# EEM_FMC_Carrier.net
KiCad netlist of a schematic drawn in Altium Designer
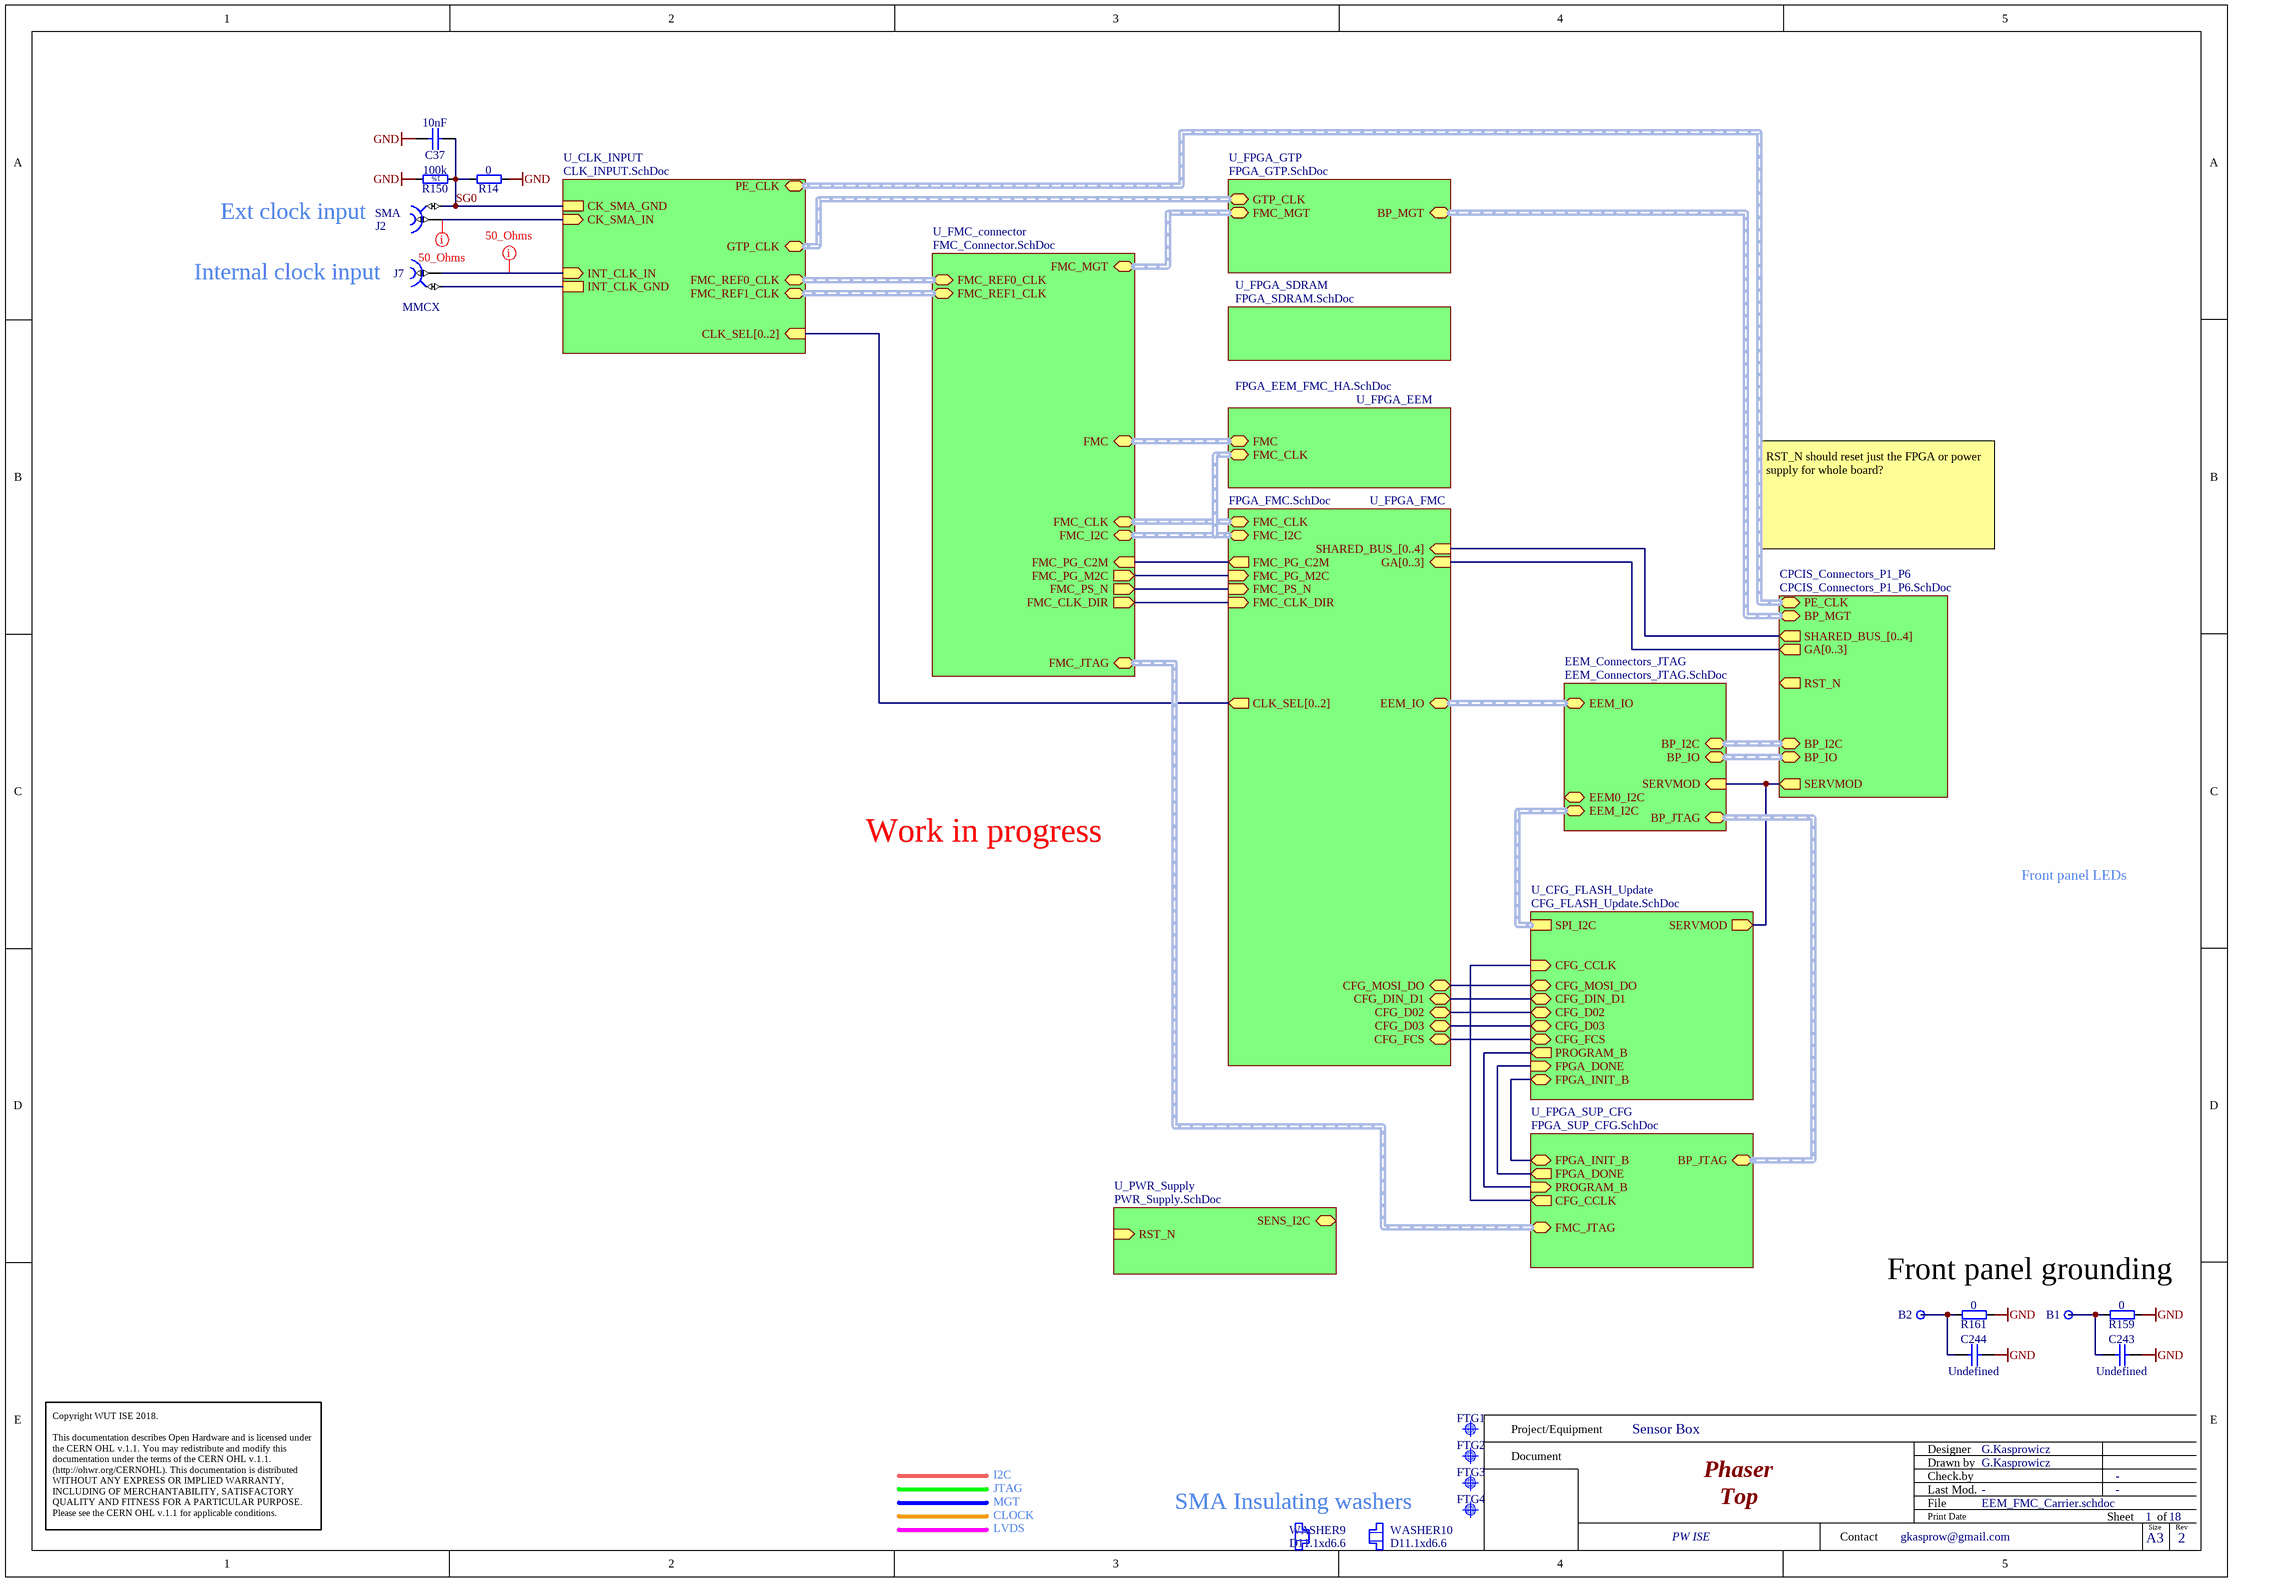
[diagram p0: EEM_FMC_Carrier.schdoc]

(export (version "E")
  (design (tool "Eeschema 10.0.6"))
  (components
    (comp (ref "B1")
      (value "Plated Hole")
      (footprint "MTG270_500")
      (description "Single Terminal Socket")
      (fields (field (name "PART NUMBER") "PLATED_HOLE2.7_PAD5.0") (field (name "AUTHOR") "CERN DEM JMW"))
      (libsource (lib "Eletro-mechanical") (part "Single Terminal Socket"))
    )
    (comp (ref "B2")
      (value "Plated Hole")
      (footprint "MTG270_500")
      (description "Single Terminal Socket")
      (fields (field (name "PART NUMBER") "PLATED_HOLE2.7_PAD5.0") (field (name "AUTHOR") "CERN DEM JMW"))
      (libsource (lib "Eletro-mechanical") (part "Single Terminal Socket"))
    )
    (comp (ref "C37")
      (value "10nF")
      (footprint "CAPC1005X55N")
      (description "Non-polarised capacitor")
      (fields
        (field (name "PART NUMBER") "CC0402_10NF_16V_10%_X7R")
        (field (name "VOLTAGE") "16V")
        (field (name "AUTHOR") "CERN DEM JLC")
      )
      (libsource (lib "Capacitors") (part "Capacitor - non polarized"))
    )
    (comp (ref "C243")
      (value "Undefined")
      (footprint "CAPC2012X135N")
      (description "Non-polarised capacitor")
      (fields (field (name "PART NUMBER") "CC0805_NO-VALUE") (field (name "AUTHOR") "CERN DEM JLC"))
      (libsource (lib "Capacitors") (part "Capacitor - non polarized"))
    )
    (comp (ref "C244")
      (value "Undefined")
      (footprint "CAPC2012X135N")
      (description "Non-polarised capacitor")
      (fields (field (name "PART NUMBER") "CC0805_NO-VALUE") (field (name "AUTHOR") "CERN DEM JLC"))
      (libsource (lib "Capacitors") (part "Capacitor - non polarized"))
    )
    (comp (ref "FTG1")
      (value "Use only in PCB")
      (footprint "FIDUCIAL_TOP_C100-200")
      (description "Fiducial Target")
      (fields (field (name "PART NUMBER") "FIDUCIAL_TARGET_C100-200") (field (name "AUTHOR") "CERN DEM JLC"))
      (libsource (lib "Eletro-mechanical") (part "Fiducial Target"))
    )
    (comp (ref "FTG2")
      (value "Use only in PCB")
      (footprint "FIDUCIAL_TOP_S100-200")
      (description "Fiducial Target")
      (fields (field (name "PART NUMBER") "FIDUCIAL_TARGET_S100-200") (field (name "AUTHOR") "CERN DEM JLC"))
      (libsource (lib "Eletro-mechanical") (part "Fiducial Target"))
    )
    (comp (ref "FTG3")
      (value "Use only in PCB")
      (footprint "FIDUCIAL_TOP_S100-200")
      (description "Fiducial Target")
      (fields (field (name "PART NUMBER") "FIDUCIAL_TARGET_S100-200") (field (name "AUTHOR") "CERN DEM JLC"))
      (libsource (lib "Eletro-mechanical") (part "Fiducial Target"))
    )
    (comp (ref "FTG4")
      (value "Use only in PCB")
      (footprint "FIDUCIAL_TOP_S100-200")
      (description "Fiducial Target")
      (fields (field (name "PART NUMBER") "FIDUCIAL_TARGET_S100-200") (field (name "AUTHOR") "CERN DEM JLC"))
      (libsource (lib "Eletro-mechanical") (part "Fiducial Target"))
    )
    (comp (ref "J2")
      (value "SMA")
      (footprint "AMPHENOL_132203-14")
      (description "50 Ohm Through Hole SMA Right Angle PCB Jack")
      (fields
        (field (name "PART NUMBER") "AMPHENOL_132203-14")
        (field (name "MANUFACTURER") "AMPHENOL")
        (field (name "AUTHOR") "GK")
      )
      (libsource (lib "Connectors") (part "CON_SMA_AMP_132203-14"))
    )
    (comp (ref "J7")
      (value "MMCX")
      (footprint "SAMTEC_MMCX-J-P-H-ST-TH1")
      (fields
        (field (name "PART NUMBER") "SAMTEC_MMCX-J-P-H-ST-TH1")
        (field (name "MANUFACTURER") "SAMTEC")
        (field (name "MANUFACTURER PART NUMBER") "MMCX-J-P-H-ST-TH1")
        (field (name "AUTHOR") "CERN DEM JLC")
      )
      (libsource (lib "Connectors") (part "Coax_1Female_1Shield"))
    )
    (comp (ref "R14")
      (value "0")
      (footprint "RESC1608X55N")
      (description "Resistor")
      (fields
        (field (name "PART NUMBER") "R0603_0R_JUMPER")
        (field (name "MANUFACTURER") "GENERIC")
        (field (name "AUTHOR") "CERN DEM JLC")
      )
      (libsource (lib "Resistors") (part "Resistor"))
    )
    (comp (ref "R150")
      (value "100k")
      (footprint "RESC1005X40N")
      (description "Resistor - 1%")
      (fields
        (field (name "PART NUMBER") "R0402_100K_1%_0.0625W_100PPM")
        (field (name "MANUFACTURER") "GENERIC")
        (field (name "AUTHOR") "CERN DEM JLC")
      )
      (libsource (lib "Resistors") (part "Resistor - 1%"))
    )
    (comp (ref "R159")
      (value "0")
      (footprint "RESC1608X55N")
      (description "Resistor")
      (fields
        (field (name "PART NUMBER") "R0603_0R_JUMPER")
        (field (name "MANUFACTURER") "GENERIC")
        (field (name "AUTHOR") "CERN DEM JLC")
      )
      (libsource (lib "Resistors") (part "Resistor"))
    )
    (comp (ref "R161")
      (value "0")
      (footprint "RESC1608X55N")
      (description "Resistor")
      (fields
        (field (name "PART NUMBER") "R0603_0R_JUMPER")
        (field (name "MANUFACTURER") "GENERIC")
        (field (name "AUTHOR") "CERN DEM JLC")
      )
      (libsource (lib "Resistors") (part "Resistor"))
    )
    (comp (ref "WASHER9")
      (value "D11.1xd6.6")
      (footprint "Keystone_7687")
      (description "SMA_Shoulder Washer")
      (fields (field (name "PART NUMBER") "custom 3D") (field (name "AUTHOR") "GK"))
      (libsource (lib "LIBRARY_SCH") (part "Keystone_7687"))
    )
    (comp (ref "WASHER10")
      (value "D11.1xd6.6")
      (footprint "Keystone_7687")
      (description "SMA_Shoulder Washer")
      (fields (field (name "PART NUMBER") "custom 3D") (field (name "AUTHOR") "GK"))
      (libsource (lib "LIBRARY_SCH") (part "Keystone_7687"))
    )
  )
  (nets
    (net (code "11") (name "/CK_SMA_IN") (class "Default")
      (node (ref "J2") (pin "1") (pinfunction "1_1") (pintype "bidirectional"))
    )
    (net (code "31") (name "/INT_CLK_GND") (class "Default")
      (node (ref "J7") (pin "2") (pinfunction "2_2") (pintype "bidirectional"))
    )
    (net (code "32") (name "/INT_CLK_IN") (class "Default")
      (node (ref "J7") (pin "1") (pinfunction "1_1") (pintype "bidirectional"))
    )
    (net (code "39") (name "/SG0") (class "Default")
      (node (ref "C37") (pin "1") (pinfunction "1_1") (pintype "passive"))
      (node (ref "J2") (pin "2") (pinfunction "2_2") (pintype "bidirectional"))
      (node (ref "R14") (pin "2") (pinfunction "2_2") (pintype "passive"))
      (node (ref "R150") (pin "2") (pinfunction "2_2") (pintype "passive"))
    )
    (net (code "41") (name "GND") (class "Default")
      (node (ref "C243") (pin "2") (pinfunction "2_2") (pintype "passive"))
      (node (ref "C244") (pin "2") (pinfunction "2_2") (pintype "passive"))
      (node (ref "C37") (pin "2") (pinfunction "2_2") (pintype "passive"))
      (node (ref "R14") (pin "1") (pinfunction "1_1") (pintype "passive"))
      (node (ref "R150") (pin "1") (pinfunction "1_1") (pintype "passive"))
      (node (ref "R159") (pin "1") (pinfunction "1_1") (pintype "passive"))
      (node (ref "R161") (pin "1") (pinfunction "1_1") (pintype "passive"))
    )
    (net (code "42") (name "Net-(B1-Pad1)") (class "Default")
      (node (ref "B1") (pin "1") (pinfunction "1_1") (pintype "bidirectional"))
      (node (ref "C243") (pin "1") (pinfunction "1_1") (pintype "passive"))
      (node (ref "R159") (pin "2") (pinfunction "2_2") (pintype "passive"))
    )
    (net (code "43") (name "Net-(B2-Pad1)") (class "Default")
      (node (ref "B2") (pin "1") (pinfunction "1_1") (pintype "bidirectional"))
      (node (ref "C244") (pin "1") (pinfunction "1_1") (pintype "passive"))
      (node (ref "R161") (pin "2") (pinfunction "2_2") (pintype "passive"))
    )
  )
)
